# board.net
KiCad netlist of a schematic drawn in EAGLE
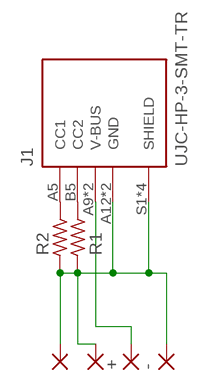
[diagram p0: schematic, sheet 1]

(export (version "E")
  (design (tool "Eeschema 10.0.6"))
  (components
    (comp (ref "+")
      (value "1,6/0,9")
      (footprint "eagle-import:1,6_0,9")
      (libsource (lib "eagle-import") (part "1,6/0,9"))
    )
    (comp (ref "-")
      (value "1,6/0,9")
      (footprint "eagle-import:1,6_0,9")
      (libsource (lib "eagle-import") (part "1,6/0,9"))
    )
    (comp (ref "J1")
      (value "UJC-HP-3-SMT-TR")
      (footprint "eagle-import:CUI_UJC-HP-3-SMT-TR")
      (fields (field (name "MF") "CUI Devices"))
      (libsource (lib "eagle-import") (part "UJC-HP-3-SMT-TR"))
    )
    (comp (ref "PAD1")
      (value "1,6/0,9")
      (footprint "eagle-import:1,6_0,9")
      (libsource (lib "eagle-import") (part "1,6/0,9"))
    )
    (comp (ref "PAD4")
      (value "1,6/0,9")
      (footprint "eagle-import:1,6_0,9")
      (libsource (lib "eagle-import") (part "1,6/0,9"))
    )
    (comp (ref "R1")
      (value "R_0402")
      (footprint "eagle-import:R0402")
      (libsource (lib "eagle-import") (part "R_0402"))
    )
    (comp (ref "R2")
      (value "R_0402")
      (footprint "eagle-import:R0402")
      (libsource (lib "eagle-import") (part "R_0402"))
    )
  )
  (nets
    (net (code "1") (name "Net-(+-P)") (class "Default")
      (node (ref "+") (pin "1") (pinfunction "P_1") (pintype "passive"))
      (node (ref "J1") (pin "A9") (pinfunction "V-BUS_A9") (pintype "power_in"))
      (node (ref "J1") (pin "B9") (pinfunction "V-BUS_B9") (pintype "power_in"))
    )
    (net (code "2") (name "Net-(--P)") (class "Default")
      (node (ref "-") (pin "1") (pinfunction "P_1") (pintype "passive"))
      (node (ref "J1") (pin "A12") (pinfunction "GND_A12") (pintype "power_in"))
      (node (ref "J1") (pin "B12") (pinfunction "GND_B12") (pintype "power_in"))
      (node (ref "J1") (pin "S1") (pinfunction "SHIELD_S1") (pintype "passive"))
      (node (ref "J1") (pin "S2") (pinfunction "SHIELD_S2") (pintype "passive"))
      (node (ref "J1") (pin "S3") (pinfunction "SHIELD_S3") (pintype "passive"))
      (node (ref "J1") (pin "S4") (pinfunction "SHIELD_S4") (pintype "passive"))
      (node (ref "PAD1") (pin "1") (pinfunction "P_1") (pintype "passive"))
      (node (ref "PAD4") (pin "1") (pinfunction "P_1") (pintype "passive"))
      (node (ref "R1") (pin "1") (pinfunction "1_1") (pintype "passive"))
      (node (ref "R2") (pin "1") (pinfunction "1_1") (pintype "passive"))
    )
    (net (code "3") (name "Net-(J1-CC1)") (class "Default")
      (node (ref "J1") (pin "A5") (pinfunction "CC1_A5") (pintype "bidirectional"))
      (node (ref "R2") (pin "2") (pinfunction "2_2") (pintype "passive"))
    )
    (net (code "4") (name "Net-(J1-CC2)") (class "Default")
      (node (ref "J1") (pin "B5") (pinfunction "CC2_B5") (pintype "bidirectional"))
      (node (ref "R1") (pin "2") (pinfunction "2_2") (pintype "passive"))
    )
  )
)
